# 2015.net
KiCad netlist of a schematic drawn in EAGLE
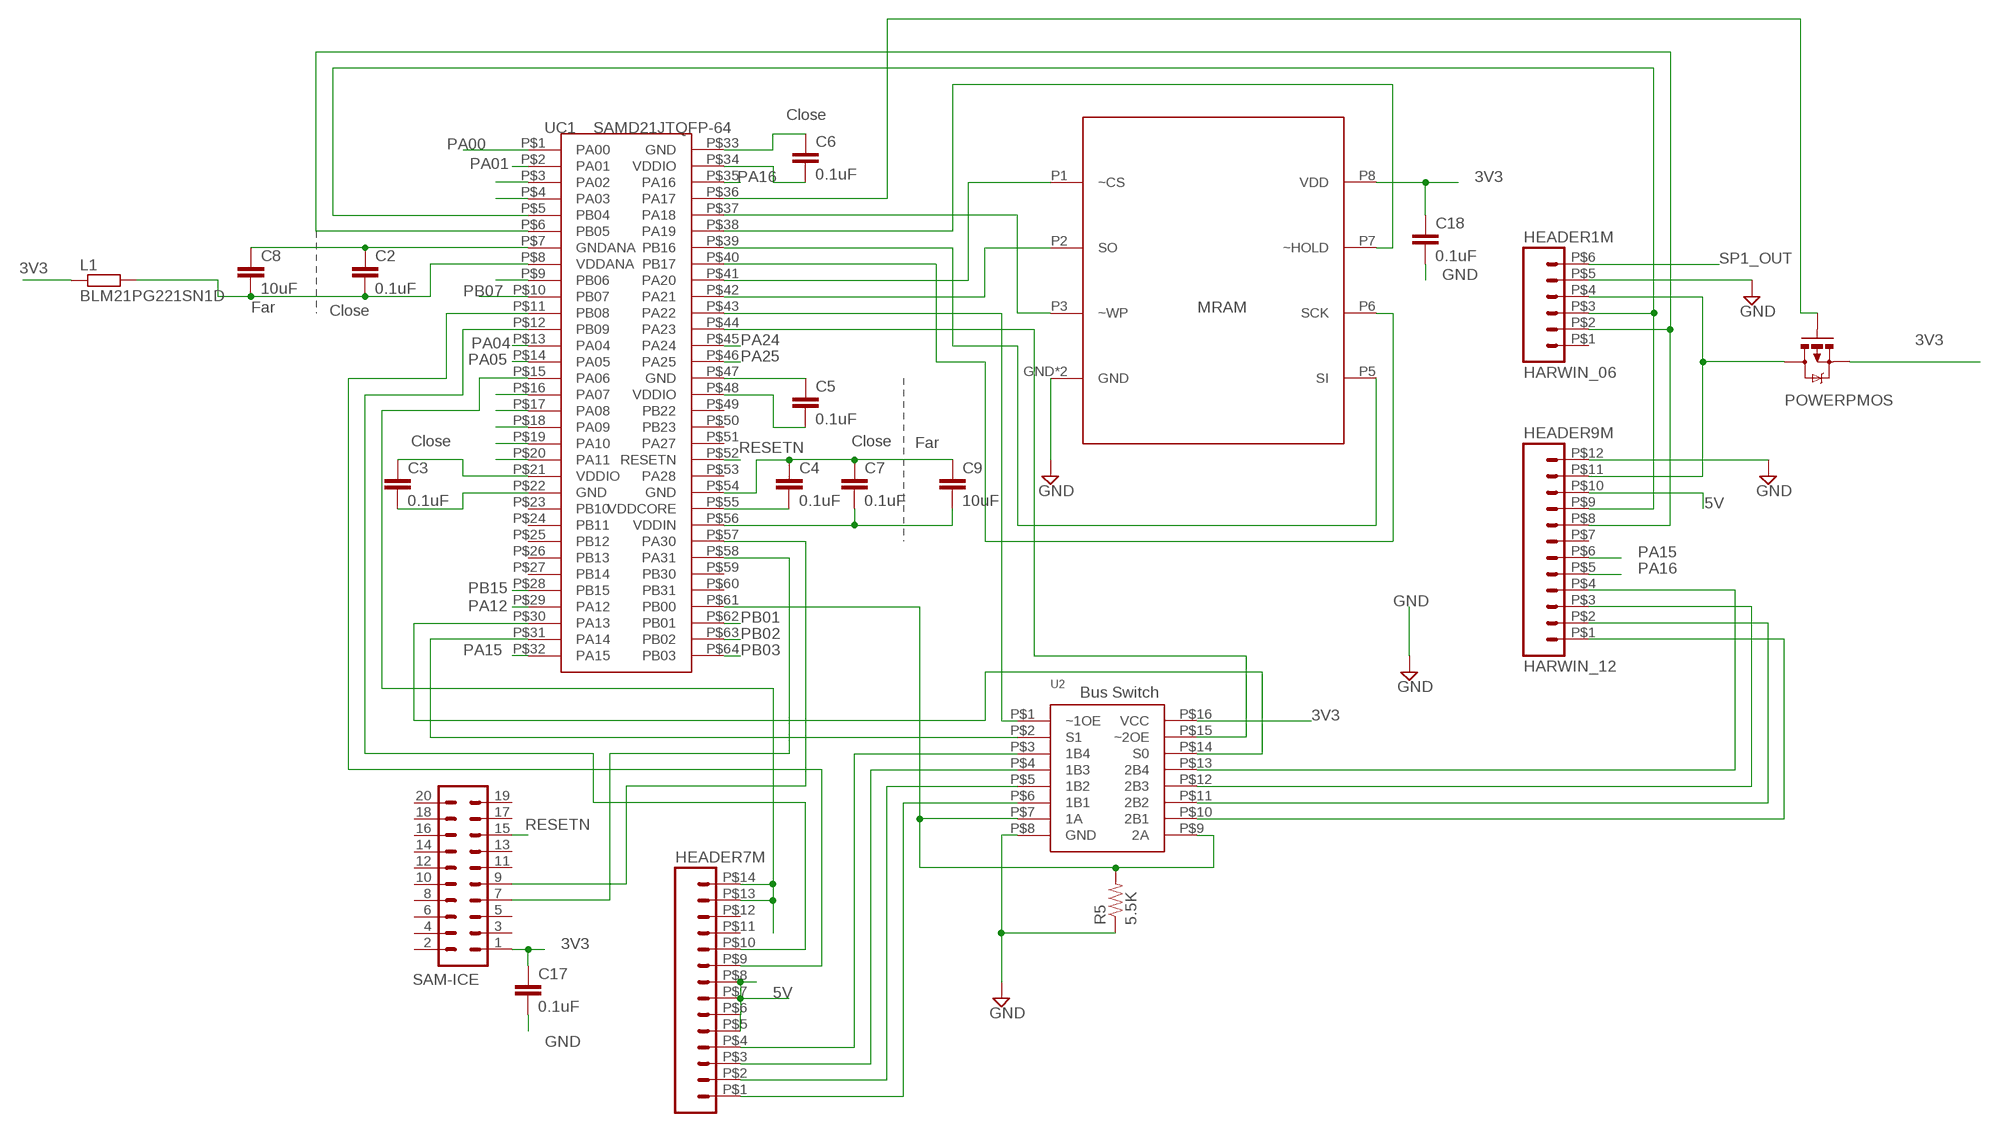
[diagram p0: schematic, sheet 1]
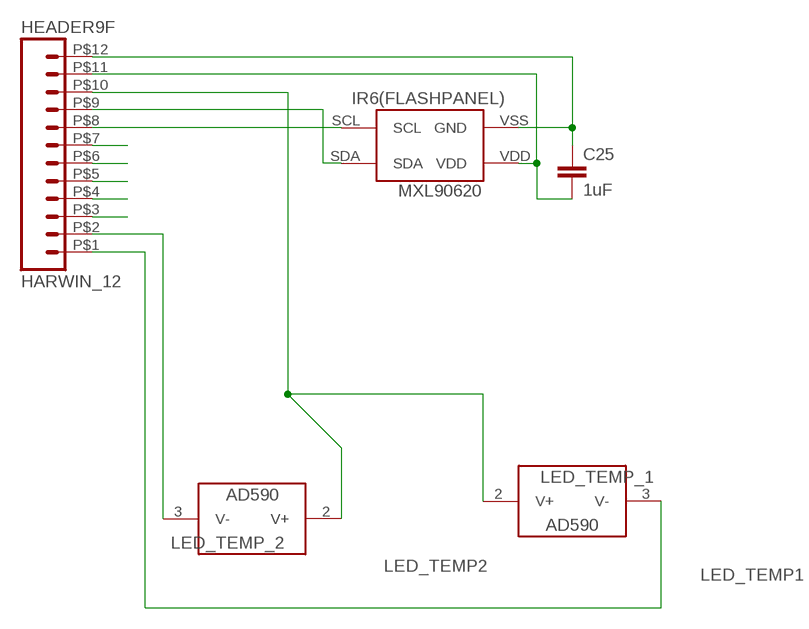
[diagram p1: schematic, sheet 2]
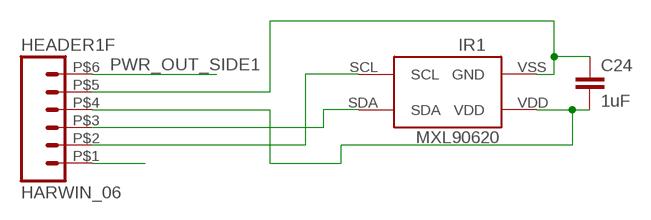
[diagram p2: schematic, sheet 3]
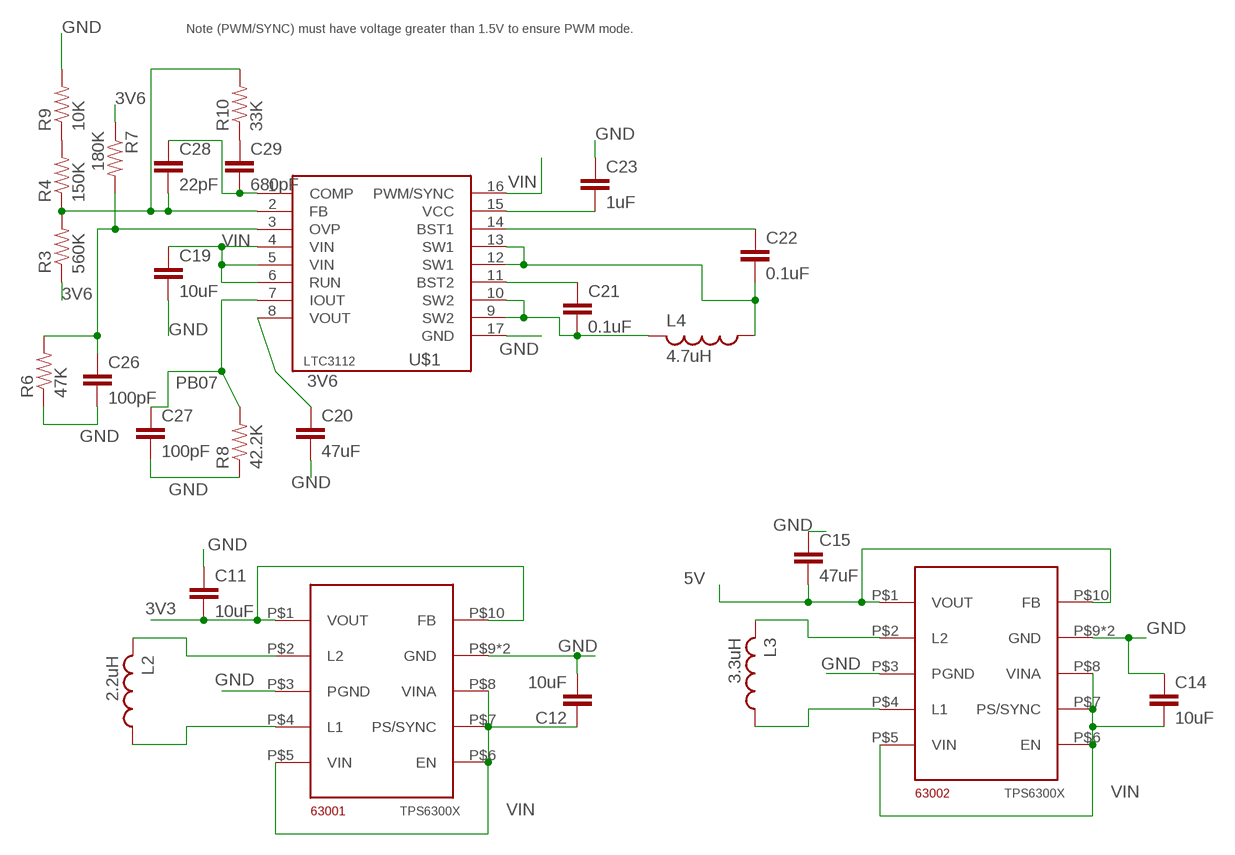
[diagram p3: schematic, sheet 4]
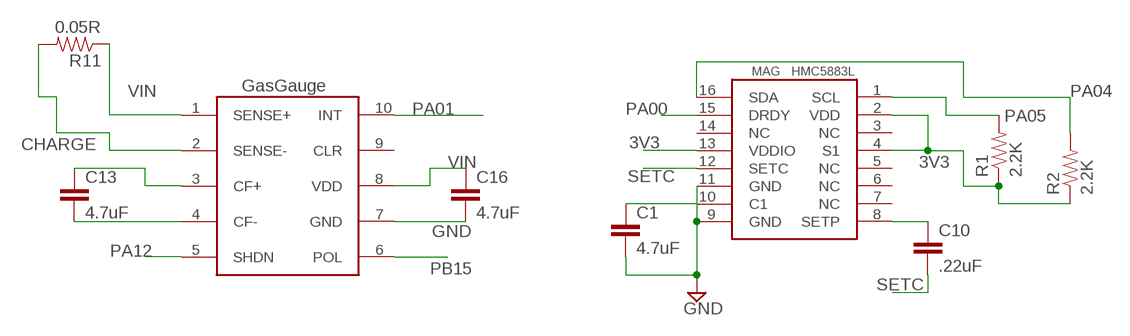
[diagram p4: schematic, sheet 5]
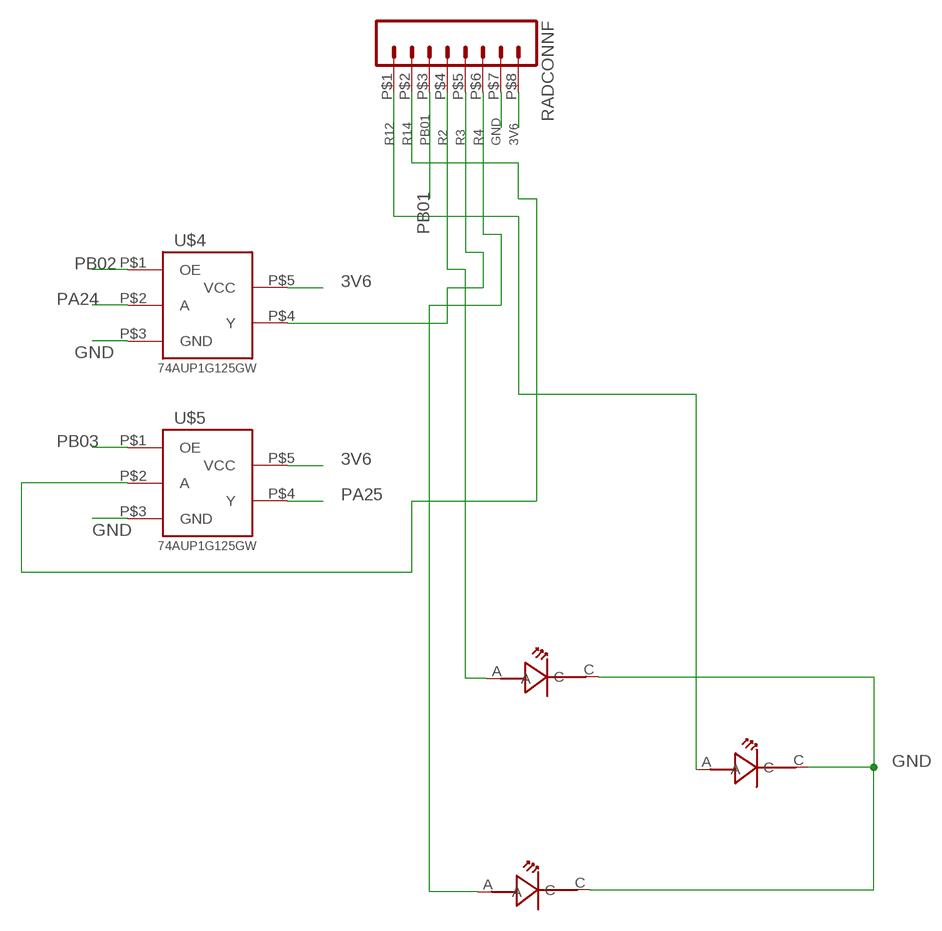
[diagram p5: schematic, sheet 6]
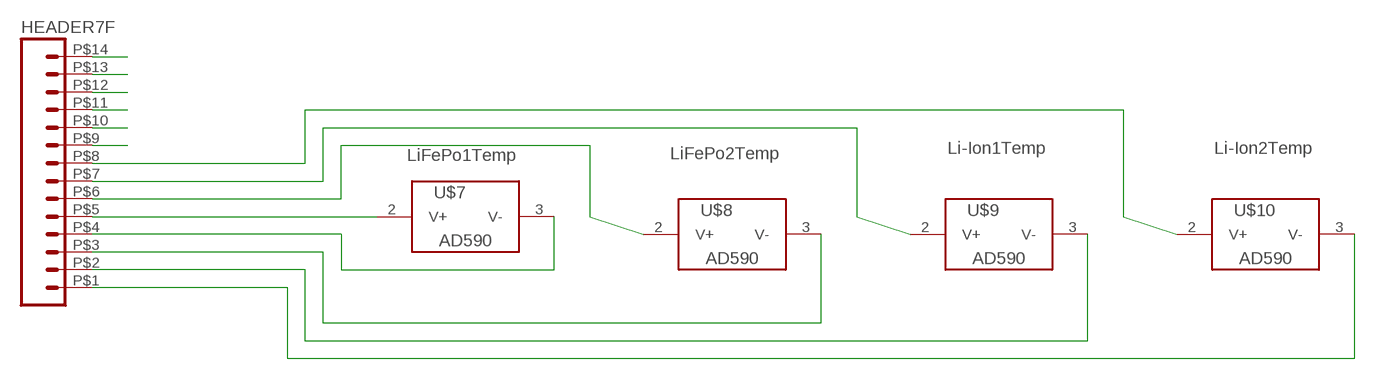
[diagram p6: schematic, sheet 7]

(export (version "E")
  (design (tool "Eeschema 10.0.6"))
  (components
    (comp (ref "63001")
      (value "TPS6300X")
      (footprint "eagle-import:QFN10_POWERPAD")
      (libsource (lib "eagle-import") (part "TPS6300X"))
    )
    (comp (ref "63002")
      (value "TPS6300X")
      (footprint "eagle-import:QFN10_POWERPAD")
      (libsource (lib "eagle-import") (part "TPS6300X"))
    )
    (comp (ref "C11")
      (value "10uF")
      (footprint "eagle-import:0603-CAP")
      (libsource (lib "eagle-import") (part "CAP0603-CAP"))
    )
    (comp (ref "C12")
      (value "10uF")
      (footprint "eagle-import:0603-CAP")
      (libsource (lib "eagle-import") (part "CAP0603-CAP"))
    )
    (comp (ref "C14")
      (value "10uF")
      (footprint "eagle-import:0603-CAP")
      (fields (field (name "MPN") "C1608X5R1A225K080AC"))
      (libsource (lib "eagle-import") (part "CAP0603-CAP"))
    )
    (comp (ref "C15")
      (value "47uF")
      (footprint "eagle-import:0603-CAP")
      (fields (field (name "MPN") "EMK107B7474KA-T"))
      (libsource (lib "eagle-import") (part "CAP0603-CAP"))
    )
    (comp (ref "C19")
      (value "10uF")
      (footprint "eagle-import:0603-CAP")
      (libsource (lib "eagle-import") (part "CAP0603-CAP"))
    )
    (comp (ref "C20")
      (value "47uF")
      (footprint "eagle-import:0805")
      (fields (field (name "MPN") "EMK107B7474KA-T"))
      (libsource (lib "eagle-import") (part "CAP0805"))
    )
    (comp (ref "C21")
      (value "0.1uF")
      (footprint "eagle-import:0603-CAP")
      (fields (field (name "MPN") "0603YC104JAT2A"))
      (libsource (lib "eagle-import") (part "CAP0603-CAP"))
    )
    (comp (ref "C22")
      (value "0.1uF")
      (footprint "eagle-import:0603-CAP")
      (fields (field (name "MPN") "0603YC104JAT2A"))
      (libsource (lib "eagle-import") (part "CAP0603-CAP"))
    )
    (comp (ref "C23")
      (value "1uF")
      (footprint "eagle-import:0603-CAP")
      (libsource (lib "eagle-import") (part "CAP0603-CAP"))
    )
    (comp (ref "C26")
      (value "100pF")
      (footprint "eagle-import:0805")
      (fields (field (name "MF") "AVX CORPORATION") (field (name "MPN") "08051A101J4T4A"))
      (libsource (lib "eagle-import") (part "CAP0805"))
    )
    (comp (ref "C27")
      (value "100pF")
      (footprint "eagle-import:0805")
      (fields (field (name "MF") "AVX CORPORATION") (field (name "MPN") "08051A101J4T4A"))
      (libsource (lib "eagle-import") (part "CAP0805"))
    )
    (comp (ref "C28")
      (value "22pF")
      (footprint "eagle-import:0805")
      (fields (field (name "MF") "AVX CORPORATION") (field (name "MPN") "08051A220JAT2A"))
      (libsource (lib "eagle-import") (part "CAP0805"))
    )
    (comp (ref "C29")
      (value "680pF")
      (footprint "eagle-import:0805")
      (fields (field (name "MPN") "08055C681KAT2A"))
      (libsource (lib "eagle-import") (part "CAP0805"))
    )
    (comp (ref "L2")
      (value "2.2uH")
      (footprint "eagle-import:L3225M")
      (libsource (lib "eagle-import") (part "L-USL3225M"))
    )
    (comp (ref "L3")
      (value "3.3uH")
      (footprint "eagle-import:L3225M")
      (fields (field (name "MPN") "JMK212BJ335KG-T"))
      (libsource (lib "eagle-import") (part "L-USL3225M"))
    )
    (comp (ref "L4")
      (value "4.7uH")
      (footprint "eagle-import:L3225M")
      (libsource (lib "eagle-import") (part "L-USL3225M"))
    )
    (comp (ref "R3")
      (value "560K")
      (footprint "eagle-import:0805")
      (fields (field (name "MPN") "MC01W08051560K"))
      (libsource (lib "eagle-import") (part "RESISTOR"))
    )
    (comp (ref "R4")
      (value "150K")
      (footprint "eagle-import:0805")
      (libsource (lib "eagle-import") (part "RESISTOR"))
    )
    (comp (ref "R6")
      (value "47K")
      (footprint "eagle-import:0805")
      (libsource (lib "eagle-import") (part "RESISTOR"))
    )
    (comp (ref "R7")
      (value "180K")
      (footprint "eagle-import:0805")
      (fields (field (name "MPN") "ERJ-6GEYJ184V"))
      (libsource (lib "eagle-import") (part "RESISTOR"))
    )
    (comp (ref "R8")
      (value "42.2K")
      (footprint "eagle-import:0805")
      (libsource (lib "eagle-import") (part "RESISTOR"))
    )
    (comp (ref "R9")
      (value "10K")
      (footprint "eagle-import:0805")
      (libsource (lib "eagle-import") (part "RESISTOR"))
    )
    (comp (ref "R10")
      (value "33K")
      (footprint "eagle-import:0805")
      (libsource (lib "eagle-import") (part "RESISTOR"))
    )
    (comp (ref "U$1")
      (value "LTC3112")
      (footprint "eagle-import:DHD16")
      (fields (field (name "MPN") "LTC3112EFE#PBF"))
      (libsource (lib "eagle-import") (part "LTC3112"))
    )
    (comp (ref "C2")
      (value "0.1uF")
      (footprint "eagle-import:0805")
      (fields (field (name "MPN") "0603YC104JAT2A"))
      (libsource (lib "eagle-import") (part "CAP0805"))
    )
    (comp (ref "C3")
      (value "0.1uF")
      (footprint "eagle-import:0805")
      (fields (field (name "MPN") "0603YC104JAT2A"))
      (libsource (lib "eagle-import") (part "CAP0805"))
    )
    (comp (ref "C4")
      (value "0.1uF")
      (footprint "eagle-import:0805")
      (fields (field (name "MPN") "0603YC104JAT2A"))
      (libsource (lib "eagle-import") (part "CAP0805"))
    )
    (comp (ref "C5")
      (value "0.1uF")
      (footprint "eagle-import:0805")
      (fields (field (name "MPN") "0603YC104JAT2A"))
      (libsource (lib "eagle-import") (part "CAP0805"))
    )
    (comp (ref "C6")
      (value "0.1uF")
      (footprint "eagle-import:0805")
      (fields (field (name "MPN") "0603YC104JAT2A"))
      (libsource (lib "eagle-import") (part "CAP0805"))
    )
    (comp (ref "C7")
      (value "0.1uF")
      (footprint "eagle-import:0805")
      (fields (field (name "MPN") "0603YC104JAT2A"))
      (libsource (lib "eagle-import") (part "CAP0805"))
    )
    (comp (ref "C8")
      (value "10uF")
      (footprint "eagle-import:0805")
      (fields (field (name "MF") "AVX CORPORATION") (field (name "MPN") "08056D106KAT2A"))
      (libsource (lib "eagle-import") (part "CAP0805"))
    )
    (comp (ref "C9")
      (value "10uF")
      (footprint "eagle-import:0805")
      (fields (field (name "MF") "AVX CORPORATION") (field (name "MPN") "08056D106KAT2A"))
      (libsource (lib "eagle-import") (part "CAP0805"))
    )
    (comp (ref "C17")
      (value "0.1uF")
      (footprint "eagle-import:0805")
      (fields (field (name "MPN") "0603YC104JAT2A"))
      (libsource (lib "eagle-import") (part "CAP0805"))
    )
    (comp (ref "C18")
      (value "0.1uF")
      (footprint "eagle-import:0805")
      (fields (field (name "MPN") "0603YC104JAT2A"))
      (libsource (lib "eagle-import") (part "CAP0805"))
    )
    (comp (ref "HEADER1M")
      (value "HARWIN_06")
      (footprint "eagle-import:HARWIN_DATAMATE_6")
      (libsource (lib "eagle-import") (part "HARWIN_06"))
    )
    (comp (ref "HEADER7M")
      (value "HARWIN_14")
      (footprint "eagle-import:HARWIN_DATAMATE_14")
      (libsource (lib "eagle-import") (part "HARWIN_14"))
    )
    (comp (ref "HEADER9M")
      (value "HARWIN_12")
      (footprint "eagle-import:HARWIN_DATAMATE_12")
      (libsource (lib "eagle-import") (part "HARWIN_12"))
    )
    (comp (ref "L1")
      (value "BLM21PG221SN1D")
      (footprint "eagle-import:R0805")
      (libsource (lib "eagle-import") (part "R-EU_R0805"))
    )
    (comp (ref "R5")
      (value "5.5K")
      (footprint "eagle-import:0805")
      (libsource (lib "eagle-import") (part "RESISTOR"))
    )
    (comp (ref "SAM-ICE")
      (value "IDC_JTAG_CONNECTOR")
      (footprint "eagle-import:2X10")
      (libsource (lib "eagle-import") (part "IDC_JTAG_CONNECTOR"))
    )
    (comp (ref "U$3")
      (value "MRAM")
      (footprint "eagle-import:8PXMO-229")
      (libsource (lib "eagle-import") (part "MR25H10CDC"))
    )
    (comp (ref "U$14")
      (value "POWERPMOS")
      (footprint "eagle-import:SO08")
      (libsource (lib "eagle-import") (part "POWERPMOS"))
    )
    (comp (ref "U2")
      (value "SN74CBTLV3253")
      (footprint "eagle-import:SOIC16R")
      (libsource (lib "eagle-import") (part "SN74CBTLV3253"))
    )
    (comp (ref "UC1")
      (value "SAMD21JTQFP-64")
      (footprint "eagle-import:TQFP-64")
      (libsource (lib "eagle-import") (part "SAMD21JTQFP-64"))
    )
    (comp (ref "C1")
      (value "4.7uF")
      (footprint "eagle-import:0805")
      (fields (field (name "MF") "AVX CORPORATION") (field (name "MPN") "08056D475KAT2A"))
      (libsource (lib "eagle-import") (part "CAP0805"))
    )
    (comp (ref "C10")
      (value ".22uF")
      (footprint "eagle-import:0805")
      (fields (field (name "MF") "AVX CORPORATION") (field (name "MPN") "08053C224KAT2A"))
      (libsource (lib "eagle-import") (part "CAP0805"))
    )
    (comp (ref "C13")
      (value "4.7uF")
      (footprint "eagle-import:0805")
      (fields (field (name "MF") "AVX CORPORATION") (field (name "MPN") "08056D475KAT2A"))
      (libsource (lib "eagle-import") (part "CAP0805"))
    )
    (comp (ref "C16")
      (value "4.7uF")
      (footprint "eagle-import:0805")
      (fields (field (name "MF") "AVX CORPORATION") (field (name "MPN") "08056D475KAT2A"))
      (libsource (lib "eagle-import") (part "CAP0805"))
    )
    (comp (ref "MAG")
      (value "HMC5883L")
      (footprint "eagle-import:HMC5883L")
      (fields (field (name "MPN") "HMC5883L-TR"))
      (libsource (lib "eagle-import") (part "HMC5883L"))
    )
    (comp (ref "R1")
      (value "2.2K")
      (footprint "eagle-import:0805")
      (fields (field (name "MPN") "SR1-0805-222"))
      (libsource (lib "eagle-import") (part "RESISTOR"))
    )
    (comp (ref "R2")
      (value "2.2K")
      (footprint "eagle-import:0805")
      (fields (field (name "MPN") "SR1-0805-222"))
      (libsource (lib "eagle-import") (part "RESISTOR"))
    )
    (comp (ref "R11")
      (value "0.05R")
      (footprint "eagle-import:0805")
      (libsource (lib "eagle-import") (part "RESISTOR"))
    )
    (comp (ref "U$2")
      (value "LTC4150")
      (footprint "eagle-import:MSOP10")
      (fields (field (name "MPN") "LTC4150CMS#PBF"))
      (libsource (lib "eagle-import") (part "LTC4150"))
    )
    (comp (ref "C25")
      (value "1uF")
      (footprint "eagle-import:0805")
      (fields (field (name "MPN") "0805ZC105KAT2A"))
      (libsource (lib "eagle-import") (part "CAP0805"))
    )
    (comp (ref "HEADER9F")
      (value "HARWIN_12")
      (footprint "eagle-import:HARWIN_DATAMATE_12")
      (libsource (lib "eagle-import") (part "HARWIN_12"))
    )
    (comp (ref "IR6(FLASHPANEL)")
      (value "MXL90620")
      (footprint "eagle-import:MXL90620")
      (libsource (lib "eagle-import") (part "MXL90620"))
    )
    (comp (ref "LED_TEMP_1")
      (value "AD590-SOIC-8")
      (footprint "eagle-import:8SOIC")
      (fields (field (name "MPN") "AD590JRZ"))
      (libsource (lib "eagle-import") (part "AD590-SOIC-8"))
    )
    (comp (ref "LED_TEMP_2")
      (value "AD590-SOIC-8")
      (footprint "eagle-import:8SOIC")
      (fields (field (name "MPN") "AD590JRZ"))
      (libsource (lib "eagle-import") (part "AD590-SOIC-8"))
    )
    (comp (ref "HEADER7F")
      (value "HARWIN_14")
      (footprint "eagle-import:HARWIN_DATAMATE_14")
      (libsource (lib "eagle-import") (part "HARWIN_14"))
    )
    (comp (ref "U$7")
      (value "AD590-SOIC-8")
      (footprint "eagle-import:8SOIC")
      (fields (field (name "MPN") "AD590JRZ"))
      (libsource (lib "eagle-import") (part "AD590-SOIC-8"))
    )
    (comp (ref "U$8")
      (value "AD590-SOIC-8")
      (footprint "eagle-import:8SOIC")
      (fields (field (name "MPN") "AD590JRZ"))
      (libsource (lib "eagle-import") (part "AD590-SOIC-8"))
    )
    (comp (ref "U$9")
      (value "AD590-SOIC-8")
      (footprint "eagle-import:8SOIC")
      (fields (field (name "MPN") "AD590JRZ"))
      (libsource (lib "eagle-import") (part "AD590-SOIC-8"))
    )
    (comp (ref "U$10")
      (value "AD590-SOIC-8")
      (footprint "eagle-import:8SOIC")
      (fields (field (name "MPN") "AD590JRZ"))
      (libsource (lib "eagle-import") (part "AD590-SOIC-8"))
    )
    (comp (ref "RADCONNF")
      (value "HARWIN_08")
      (footprint "eagle-import:HARWIN_DATAMATE_08")
      (libsource (lib "eagle-import") (part "HARWIN_08"))
    )
    (comp (ref "U$4")
      (value "74AUP1G125GW")
      (footprint "eagle-import:TSSOP-5")
      (libsource (lib "eagle-import") (part "74AUP1G125GW"))
    )
    (comp (ref "U$5")
      (value "74AUP1G125GW")
      (footprint "eagle-import:TSSOP-5")
      (libsource (lib "eagle-import") (part "74AUP1G125GW"))
    )
    (comp (ref "U$11")
      (value "LT-T673-Q1R2-25-Z")
      (footprint "eagle-import:PLCC-2")
      (libsource (lib "eagle-import") (part "LT-T673-Q1R2-25-Z"))
    )
    (comp (ref "U$12")
      (value "LT-T673-Q1R2-25-Z")
      (footprint "eagle-import:PLCC-2")
      (libsource (lib "eagle-import") (part "LT-T673-Q1R2-25-Z"))
    )
    (comp (ref "U$13")
      (value "LT-T673-Q1R2-25-Z")
      (footprint "eagle-import:PLCC-2")
      (libsource (lib "eagle-import") (part "LT-T673-Q1R2-25-Z"))
    )
    (comp (ref "C24")
      (value "1uF")
      (footprint "eagle-import:0805")
      (fields (field (name "MPN") "0805ZC105KAT2A"))
      (libsource (lib "eagle-import") (part "CAP0805"))
    )
    (comp (ref "HEADER1F")
      (value "HARWIN_06")
      (footprint "eagle-import:HARWIN_DATAMATE_6")
      (libsource (lib "eagle-import") (part "HARWIN_06"))
    )
    (comp (ref "IR1")
      (value "MXL90620")
      (footprint "eagle-import:MXL90620")
      (libsource (lib "eagle-import") (part "MXL90620"))
    )
  )
  (nets
    (net (code "1") (name "3V3") (class "Default")
      (node (ref "63001") (pin "P$1") (pinfunction "VOUT_P$1") (pintype "output"))
      (node (ref "63001") (pin "P$10") (pinfunction "FB_P$10") (pintype "input"))
      (node (ref "C11") (pin "2") (pinfunction "2_2") (pintype "passive"))
      (node (ref "C17") (pin "1") (pinfunction "1_1") (pintype "passive"))
      (node (ref "C18") (pin "1") (pinfunction "1_1") (pintype "passive"))
      (node (ref "C3") (pin "1") (pinfunction "1_1") (pintype "passive"))
      (node (ref "C5") (pin "2") (pinfunction "2_2") (pintype "passive"))
      (node (ref "C6") (pin "2") (pinfunction "2_2") (pintype "passive"))
      (node (ref "C7") (pin "2") (pinfunction "2_2") (pintype "passive"))
      (node (ref "C9") (pin "2") (pinfunction "2_2") (pintype "passive"))
      (node (ref "L1") (pin "1") (pinfunction "1_1") (pintype "passive"))
      (node (ref "MAG") (pin "13") (pinfunction "VDDIO_13") (pintype "bidirectional"))
      (node (ref "MAG") (pin "2") (pinfunction "VDD_2") (pintype "bidirectional"))
      (node (ref "MAG") (pin "4") (pinfunction "S1_4") (pintype "bidirectional"))
      (node (ref "R1") (pin "1") (pinfunction "1_1") (pintype "passive"))
      (node (ref "R2") (pin "1") (pinfunction "1_1") (pintype "passive"))
      (node (ref "SAM-ICE") (pin "1") (pinfunction "1_1") (pintype "passive"))
      (node (ref "U$14") (pin "1") (pinfunction "S_1") (pintype "passive"))
      (node (ref "U$14") (pin "2") (pinfunction "S_2") (pintype "passive"))
      (node (ref "U$14") (pin "3") (pinfunction "S_3") (pintype "passive"))
      (node (ref "U$3") (pin "P8") (pinfunction "VDD_P8") (pintype "bidirectional"))
      (node (ref "U2") (pin "P$16") (pinfunction "VCC_P$16") (pintype "bidirectional"))
      (node (ref "UC1") (pin "P$21") (pinfunction "VDDIO_P$21") (pintype "power_in"))
      (node (ref "UC1") (pin "P$34") (pinfunction "VDDIO_P$34") (pintype "power_in"))
      (node (ref "UC1") (pin "P$48") (pinfunction "VDDIO_P$48") (pintype "power_in"))
      (node (ref "UC1") (pin "P$56") (pinfunction "VDDIN_P$56") (pintype "power_in"))
    )
    (net (code "2") (name "3V6") (class "Default")
      (node (ref "C20") (pin "1") (pinfunction "1_1") (pintype "passive"))
      (node (ref "R3") (pin "1") (pinfunction "1_1") (pintype "passive"))
      (node (ref "R7") (pin "1") (pinfunction "1_1") (pintype "passive"))
      (node (ref "RADCONNF") (pin "P$8") (pinfunction "8_P$8") (pintype "passive"))
      (node (ref "U$1") (pin "8") (pinfunction "VOUT_8") (pintype "bidirectional"))
      (node (ref "U$4") (pin "P$5") (pinfunction "VCC_P$5") (pintype "bidirectional"))
      (node (ref "U$5") (pin "P$5") (pinfunction "VCC_P$5") (pintype "bidirectional"))
    )
    (net (code "3") (name "5V") (class "Default")
      (node (ref "63002") (pin "P$1") (pinfunction "VOUT_P$1") (pintype "output"))
      (node (ref "63002") (pin "P$10") (pinfunction "FB_P$10") (pintype "input"))
      (node (ref "C15") (pin "2") (pinfunction "2_2") (pintype "passive"))
      (node (ref "HEADER7M") (pin "P$5") (pinfunction "5_P$5") (pintype "passive"))
      (node (ref "HEADER7M") (pin "P$6") (pinfunction "6_P$6") (pintype "passive"))
      (node (ref "HEADER7M") (pin "P$7") (pinfunction "7_P$7") (pintype "passive"))
      (node (ref "HEADER7M") (pin "P$8") (pinfunction "8_P$8") (pintype "passive"))
      (node (ref "HEADER9M") (pin "P$10") (pinfunction "10_P$10") (pintype "passive"))
    )
    (net (code "4") (name "CHARGE") (class "Default")
      (node (ref "R11") (pin "2") (pinfunction "2_2") (pintype "passive"))
      (node (ref "U$2") (pin "2") (pinfunction "SENSE-_2") (pintype "bidirectional"))
    )
    (net (code "5") (name "GND") (class "Default")
      (node (ref "63001") (pin "P$3") (pinfunction "PGND_P$3") (pintype "input"))
      (node (ref "63001") (pin "P$9") (pinfunction "GND_P$9") (pintype "input"))
      (node (ref "63001") (pin "PAD") (pinfunction "GND_PAD") (pintype "input"))
      (node (ref "63002") (pin "P$3") (pinfunction "PGND_P$3") (pintype "input"))
      (node (ref "63002") (pin "P$9") (pinfunction "GND_P$9") (pintype "input"))
      (node (ref "63002") (pin "PAD") (pinfunction "GND_PAD") (pintype "input"))
      (node (ref "C1") (pin "2") (pinfunction "2_2") (pintype "passive"))
      (node (ref "C11") (pin "1") (pinfunction "1_1") (pintype "passive"))
      (node (ref "C12") (pin "2") (pinfunction "2_2") (pintype "passive"))
      (node (ref "C14") (pin "1") (pinfunction "1_1") (pintype "passive"))
      (node (ref "C15") (pin "1") (pinfunction "1_1") (pintype "passive"))
      (node (ref "C16") (pin "2") (pinfunction "2_2") (pintype "passive"))
      (node (ref "C17") (pin "2") (pinfunction "2_2") (pintype "passive"))
      (node (ref "C18") (pin "2") (pinfunction "2_2") (pintype "passive"))
      (node (ref "C19") (pin "2") (pinfunction "2_2") (pintype "passive"))
      (node (ref "C2") (pin "1") (pinfunction "1_1") (pintype "passive"))
      (node (ref "C20") (pin "2") (pinfunction "2_2") (pintype "passive"))
      (node (ref "C23") (pin "1") (pinfunction "1_1") (pintype "passive"))
      (node (ref "C26") (pin "2") (pinfunction "2_2") (pintype "passive"))
      (node (ref "C27") (pin "2") (pinfunction "2_2") (pintype "passive"))
      (node (ref "C4") (pin "1") (pinfunction "1_1") (pintype "passive"))
      (node (ref "C5") (pin "1") (pinfunction "1_1") (pintype "passive"))
      (node (ref "C6") (pin "1") (pinfunction "1_1") (pintype "passive"))
      (node (ref "C7") (pin "1") (pinfunction "1_1") (pintype "passive"))
      (node (ref "C8") (pin "1") (pinfunction "1_1") (pintype "passive"))
      (node (ref "C9") (pin "1") (pinfunction "1_1") (pintype "passive"))
      (node (ref "HEADER1M") (pin "P$5") (pinfunction "5_P$5") (pintype "passive"))
      (node (ref "HEADER9M") (pin "P$12") (pinfunction "12_P$12") (pintype "passive"))
      (node (ref "MAG") (pin "11") (pinfunction "GND_11") (pintype "bidirectional"))
      (node (ref "MAG") (pin "9") (pinfunction "GND_9") (pintype "bidirectional"))
      (node (ref "R5") (pin "1") (pinfunction "1_1") (pintype "passive"))
      (node (ref "R6") (pin "1") (pinfunction "1_1") (pintype "passive"))
      (node (ref "R8") (pin "1") (pinfunction "1_1") (pintype "passive"))
      (node (ref "R9") (pin "2") (pinfunction "2_2") (pintype "passive"))
      (node (ref "RADCONNF") (pin "P$7") (pinfunction "7_P$7") (pintype "passive"))
      (node (ref "U$1") (pin "17") (pinfunction "GND_17") (pintype "bidirectional"))
      (node (ref "U$11") (pin "C") (pinfunction "C_C") (pintype "bidirectional"))
      (node (ref "U$12") (pin "C") (pinfunction "C_C") (pintype "bidirectional"))
      (node (ref "U$13") (pin "C") (pinfunction "C_C") (pintype "bidirectional"))
      (node (ref "U$2") (pin "7") (pinfunction "GND_7") (pintype "bidirectional"))
      (node (ref "U$3") (pin "GND") (pinfunction "GND_GND") (pintype "bidirectional"))
      (node (ref "U$3") (pin "P4") (pinfunction "GND_P4") (pintype "bidirectional"))
      (node (ref "U$4") (pin "P$3") (pinfunction "GND_P$3") (pintype "bidirectional"))
      (node (ref "U$5") (pin "P$3") (pinfunction "GND_P$3") (pintype "bidirectional"))
      (node (ref "U2") (pin "P$8") (pinfunction "GND_P$8") (pintype "bidirectional"))
      (node (ref "UC1") (pin "P$33") (pinfunction "GND_P$33") (pintype "power_in"))
      (node (ref "UC1") (pin "P$47") (pinfunction "GND_P$47") (pintype "power_in"))
      (node (ref "UC1") (pin "P$54") (pinfunction "GND_P$54") (pintype "power_in"))
      (node (ref "UC1") (pin "P$7") (pinfunction "GNDANA_P$7") (pintype "power_in"))
    )
    (net (code "6") (name "Net-(63001-L1)") (class "Default")
      (node (ref "63001") (pin "P$4") (pinfunction "L1_P$4") (pintype "input"))
      (node (ref "L2") (pin "1") (pinfunction "1_1") (pintype "passive"))
    )
    (net (code "7") (name "Net-(63001-L2)") (class "Default")
      (node (ref "63001") (pin "P$2") (pinfunction "L2_P$2") (pintype "input"))
      (node (ref "L2") (pin "2") (pinfunction "2_2") (pintype "passive"))
    )
    (net (code "8") (name "Net-(63002-L1)") (class "Default")
      (node (ref "63002") (pin "P$4") (pinfunction "L1_P$4") (pintype "input"))
      (node (ref "L3") (pin "1") (pinfunction "1_1") (pintype "passive"))
    )
    (net (code "9") (name "Net-(63002-L2)") (class "Default")
      (node (ref "63002") (pin "P$2") (pinfunction "L2_P$2") (pintype "input"))
      (node (ref "L3") (pin "2") (pinfunction "2_2") (pintype "passive"))
    )
    (net (code "10") (name "Net-(C3-Pad2)") (class "Default")
      (node (ref "C3") (pin "2") (pinfunction "2_2") (pintype "passive"))
      (node (ref "UC1") (pin "P$22") (pinfunction "GND_P$22") (pintype "power_in"))
    )
    (net (code "11") (name "Net-(C21-Pad2)") (class "Default")
      (node (ref "C21") (pin "2") (pinfunction "2_2") (pintype "passive"))
      (node (ref "L4") (pin "2") (pinfunction "2_2") (pintype "passive"))
      (node (ref "U$1") (pin "10") (pinfunction "SW2_10") (pintype "bidirectional"))
      (node (ref "U$1") (pin "9") (pinfunction "SW2_9") (pintype "bidirectional"))
    )
    (net (code "12") (name "Net-(C22-Pad2)") (class "Default")
      (node (ref "C22") (pin "2") (pinfunction "2_2") (pintype "passive"))
      (node (ref "L4") (pin "1") (pinfunction "1_1") (pintype "passive"))
      (node (ref "U$1") (pin "12") (pinfunction "SW1_12") (pintype "bidirectional"))
      (node (ref "U$1") (pin "13") (pinfunction "SW1_13") (pintype "bidirectional"))
    )
    (net (code "13") (name "Net-(C29-Pad1)") (class "Default")
      (node (ref "C29") (pin "1") (pinfunction "1_1") (pintype "passive"))
      (node (ref "R10") (pin "1") (pinfunction "1_1") (pintype "passive"))
    )
    (net (code "14") (name "Net-(HEADER1F-2)") (class "Default")
      (node (ref "HEADER1F") (pin "P$2") (pinfunction "2_P$2") (pintype "passive"))
      (node (ref "IR1") (pin "SCL") (pinfunction "SCL_SCL") (pintype "bidirectional"))
    )
    (net (code "15") (name "Net-(HEADER1F-3)") (class "Default")
      (node (ref "HEADER1F") (pin "P$3") (pinfunction "3_P$3") (pintype "passive"))
      (node (ref "IR1") (pin "SDA") (pinfunction "SDA_SDA") (pintype "bidirectional"))
    )
    (net (code "16") (name "Net-(HEADER1F-4)") (class "Default")
      (node (ref "C24") (pin "2") (pinfunction "2_2") (pintype "passive"))
      (node (ref "HEADER1F") (pin "P$4") (pinfunction "4_P$4") (pintype "passive"))
      (node (ref "IR1") (pin "VDD") (pinfunction "VDD_VDD") (pintype "bidirectional"))
    )
    (net (code "17") (name "Net-(HEADER1F-5)") (class "Default")
      (node (ref "C24") (pin "1") (pinfunction "1_1") (pintype "passive"))
      (node (ref "HEADER1F") (pin "P$5") (pinfunction "5_P$5") (pintype "passive"))
      (node (ref "IR1") (pin "VSS") (pinfunction "GND_VSS") (pintype "bidirectional"))
    )
    (net (code "18") (name "Net-(HEADER1M-2)") (class "Default")
      (node (ref "HEADER1M") (pin "P$2") (pinfunction "2_P$2") (pintype "passive"))
      (node (ref "HEADER9M") (pin "P$8") (pinfunction "8_P$8") (pintype "passive"))
      (node (ref "UC1") (pin "P$6") (pinfunction "PB05_P$6") (pintype "bidirectional"))
    )
    (net (code "19") (name "Net-(HEADER1M-3)") (class "Default")
      (node (ref "HEADER1M") (pin "P$3") (pinfunction "3_P$3") (pintype "passive"))
      (node (ref "HEADER9M") (pin "P$9") (pinfunction "9_P$9") (pintype "passive"))
      (node (ref "UC1") (pin "P$5") (pinfunction "PB04_P$5") (pintype "bidirectional"))
    )
    (net (code "20") (name "Net-(HEADER1M-4)") (class "Default")
      (node (ref "HEADER1M") (pin "P$4") (pinfunction "4_P$4") (pintype "passive"))
      (node (ref "HEADER9M") (pin "P$11") (pinfunction "11_P$11") (pintype "passive"))
      (node (ref "U$14") (pin "5") (pinfunction "D_5") (pintype "passive"))
      (node (ref "U$14") (pin "6") (pinfunction "D_6") (pintype "passive"))
      (node (ref "U$14") (pin "7") (pinfunction "D_7") (pintype "passive"))
      (node (ref "U$14") (pin "8") (pinfunction "D_8") (pintype "passive"))
    )
    (net (code "21") (name "Net-(HEADER7F-1)") (class "Default")
      (node (ref "HEADER7F") (pin "P$1") (pinfunction "1_P$1") (pintype "passive"))
      (node (ref "U$10") (pin "3") (pinfunction "V-_3") (pintype "bidirectional"))
    )
    (net (code "22") (name "Net-(HEADER7F-2)") (class "Default")
      (node (ref "HEADER7F") (pin "P$2") (pinfunction "2_P$2") (pintype "passive"))
      (node (ref "U$9") (pin "3") (pinfunction "V-_3") (pintype "bidirectional"))
    )
    (net (code "23") (name "Net-(HEADER7F-3)") (class "Default")
      (node (ref "HEADER7F") (pin "P$3") (pinfunction "3_P$3") (pintype "passive"))
      (node (ref "U$8") (pin "3") (pinfunction "V-_3") (pintype "bidirectional"))
    )
    (net (code "24") (name "Net-(HEADER7F-4)") (class "Default")
      (node (ref "HEADER7F") (pin "P$4") (pinfunction "4_P$4") (pintype "passive"))
      (node (ref "U$7") (pin "3") (pinfunction "V-_3") (pintype "bidirectional"))
    )
    (net (code "25") (name "Net-(HEADER7F-5)") (class "Default")
      (node (ref "HEADER7F") (pin "P$5") (pinfunction "5_P$5") (pintype "passive"))
      (node (ref "U$7") (pin "2") (pinfunction "V+_2") (pintype "bidirectional"))
    )
    (net (code "26") (name "Net-(HEADER7F-6)") (class "Default")
      (node (ref "HEADER7F") (pin "P$6") (pinfunction "6_P$6") (pintype "passive"))
      (node (ref "U$8") (pin "2") (pinfunction "V+_2") (pintype "bidirectional"))
    )
    (net (code "27") (name "Net-(HEADER7F-7)") (class "Default")
      (node (ref "HEADER7F") (pin "P$7") (pinfunction "7_P$7") (pintype "passive"))
      (node (ref "U$9") (pin "2") (pinfunction "V+_2") (pintype "bidirectional"))
    )
    (net (code "28") (name "Net-(HEADER7F-8)") (class "Default")
      (node (ref "HEADER7F") (pin "P$8") (pinfunction "8_P$8") (pintype "passive"))
      (node (ref "U$10") (pin "2") (pinfunction "V+_2") (pintype "bidirectional"))
    )
    (net (code "29") (name "Net-(HEADER7M-1)") (class "Default")
      (node (ref "HEADER7M") (pin "P$1") (pinfunction "1_P$1") (pintype "passive"))
      (node (ref "U2") (pin "P$6") (pinfunction "1B1_P$6") (pintype "bidirectional"))
    )
    (net (code "30") (name "Net-(HEADER7M-2)") (class "Default")
      (node (ref "HEADER7M") (pin "P$2") (pinfunction "2_P$2") (pintype "passive"))
      (node (ref "U2") (pin "P$5") (pinfunction "1B2_P$5") (pintype "bidirectional"))
    )
    (net (code "31") (name "Net-(HEADER7M-3)") (class "Default")
      (node (ref "HEADER7M") (pin "P$3") (pinfunction "3_P$3") (pintype "passive"))
      (node (ref "U2") (pin "P$4") (pinfunction "1B3_P$4") (pintype "bidirectional"))
    )
    (net (code "32") (name "Net-(HEADER7M-4)") (class "Default")
      (node (ref "HEADER7M") (pin "P$4") (pinfunction "4_P$4") (pintype "passive"))
      (node (ref "U2") (pin "P$3") (pinfunction "1B4_P$3") (pintype "bidirectional"))
    )
    (net (code "33") (name "Net-(HEADER7M-9)") (class "Default")
      (node (ref "HEADER7M") (pin "P$9") (pinfunction "9_P$9") (pintype "passive"))
      (node (ref "UC1") (pin "P$11") (pinfunction "PB08_P$11") (pintype "bidirectional"))
    )
    (net (code "34") (name "Net-(HEADER7M-10)") (class "Default")
      (node (ref "HEADER7M") (pin "P$10") (pinfunction "10_P$10") (pintype "passive"))
      (node (ref "UC1") (pin "P$12") (pinfunction "PB09_P$12") (pintype "bidirectional"))
    )
    (net (code "35") (name "Net-(HEADER7M-13)") (class "Default")
      (node (ref "HEADER7M") (pin "P$13") (pinfunction "13_P$13") (pintype "passive"))
      (node (ref "HEADER7M") (pin "P$14") (pinfunction "14_P$14") (pintype "passive"))
      (node (ref "UC1") (pin "P$15") (pinfunction "PA06_P$15") (pintype "bidirectional"))
    )
    (net (code "36") (name "Net-(HEADER9F-1)") (class "Default")
      (node (ref "HEADER9F") (pin "P$1") (pinfunction "1_P$1") (pintype "passive"))
      (node (ref "LED_TEMP_1") (pin "3") (pinfunction "V-_3") (pintype "bidirectional"))
    )
    (net (code "37") (name "Net-(HEADER9F-2)") (class "Default")
      (node (ref "HEADER9F") (pin "P$2") (pinfunction "2_P$2") (pintype "passive"))
      (node (ref "LED_TEMP_2") (pin "3") (pinfunction "V-_3") (pintype "bidirectional"))
    )
    (net (code "38") (name "Net-(HEADER9F-8)") (class "Default")
      (node (ref "HEADER9F") (pin "P$8") (pinfunction "8_P$8") (pintype "passive"))
      (node (ref "IR6(FLASHPANEL)") (pin "SCL") (pinfunction "SCL_SCL") (pintype "bidirectional"))
    )
    (net (code "39") (name "Net-(HEADER9F-9)") (class "Default")
      (node (ref "HEADER9F") (pin "P$9") (pinfunction "9_P$9") (pintype "passive"))
      (node (ref "IR6(FLASHPANEL)") (pin "SDA") (pinfunction "SDA_SDA") (pintype "bidirectional"))
    )
    (net (code "40") (name "Net-(HEADER9F-10)") (class "Default")
      (node (ref "HEADER9F") (pin "P$10") (pinfunction "10_P$10") (pintype "passive"))
      (node (ref "LED_TEMP_1") (pin "2") (pinfunction "V+_2") (pintype "bidirectional"))
      (node (ref "LED_TEMP_2") (pin "2") (pinfunction "V+_2") (pintype "bidirectional"))
    )
    (net (code "41") (name "Net-(HEADER9F-11)") (class "Default")
      (node (ref "C25") (pin "2") (pinfunction "2_2") (pintype "passive"))
      (node (ref "HEADER9F") (pin "P$11") (pinfunction "11_P$11") (pintype "passive"))
      (node (ref "IR6(FLASHPANEL)") (pin "VDD") (pinfunction "VDD_VDD") (pintype "bidirectional"))
    )
    (net (code "42") (name "Net-(HEADER9F-12)") (class "Default")
      (node (ref "C25") (pin "1") (pinfunction "1_1") (pintype "passive"))
      (node (ref "HEADER9F") (pin "P$12") (pinfunction "12_P$12") (pintype "passive"))
      (node (ref "IR6(FLASHPANEL)") (pin "VSS") (pinfunction "GND_VSS") (pintype "bidirectional"))
    )
    (net (code "43") (name "Net-(HEADER9M-1)") (class "Default")
      (node (ref "HEADER9M") (pin "P$1") (pinfunction "1_P$1") (pintype "passive"))
      (node (ref "U2") (pin "P$10") (pinfunction "2B1_P$10") (pintype "bidirectional"))
    )
    (net (code "44") (name "Net-(HEADER9M-2)") (class "Default")
      (node (ref "HEADER9M") (pin "P$2") (pinfunction "2_P$2") (pintype "passive"))
      (node (ref "U2") (pin "P$11") (pinfunction "2B2_P$11") (pintype "bidirectional"))
    )
    (net (code "45") (name "Net-(HEADER9M-3)") (class "Default")
      (node (ref "HEADER9M") (pin "P$3") (pinfunction "3_P$3") (pintype "passive"))
      (node (ref "U2") (pin "P$12") (pinfunction "2B3_P$12") (pintype "bidirectional"))
    )
    (net (code "46") (name "Net-(HEADER9M-4)") (class "Default")
      (node (ref "HEADER9M") (pin "P$4") (pinfunction "4_P$4") (pintype "passive"))
      (node (ref "U2") (pin "P$13") (pinfunction "2B4_P$13") (pintype "bidirectional"))
    )
    (net (code "47") (name "Net-(MAG-C1)") (class "Default")
      (node (ref "C1") (pin "1") (pinfunction "1_1") (pintype "passive"))
      (node (ref "MAG") (pin "10") (pinfunction "C1_10") (pintype "bidirectional"))
    )
    (net (code "48") (name "Net-(MAG-SETP)") (class "Default")
      (node (ref "C10") (pin "1") (pinfunction "1_1") (pintype "passive"))
      (node (ref "MAG") (pin "8") (pinfunction "SETP_8") (pintype "bidirectional"))
    )
    (net (code "49") (name "Net-(R4-Pad2)") (class "Default")
      (node (ref "R4") (pin "2") (pinfunction "2_2") (pintype "passive"))
      (node (ref "R9") (pin "1") (pinfunction "1_1") (pintype "passive"))
    )
    (net (code "50") (name "Net-(U$1-BST1)") (class "Default")
      (node (ref "C22") (pin "1") (pinfunction "1_1") (pintype "passive"))
      (node (ref "U$1") (pin "14") (pinfunction "BST1_14") (pintype "bidirectional"))
    )
    (net (code "51") (name "Net-(U$1-BST2)") (class "Default")
      (node (ref "C21") (pin "1") (pinfunction "1_1") (pintype "passive"))
      (node (ref "U$1") (pin "11") (pinfunction "BST2_11") (pintype "bidirectional"))
    )
    (net (code "52") (name "Net-(U$1-COMP)") (class "Default")
      (node (ref "C28") (pin "1") (pinfunction "1_1") (pintype "passive"))
      (node (ref "C29") (pin "2") (pinfunction "2_2") (pintype "passive"))
      (node (ref "U$1") (pin "1") (pinfunction "COMP_1") (pintype "bidirectional"))
    )
    (net (code "53") (name "Net-(U$1-FB)") (class "Default")
      (node (ref "C28") (pin "2") (pinfunction "2_2") (pintype "passive"))
      (node (ref "R10") (pin "2") (pinfunction "2_2") (pintype "passive"))
      (node (ref "R3") (pin "2") (pinfunction "2_2") (pintype "passive"))
      (node (ref "R4") (pin "1") (pinfunction "1_1") (pintype "passive"))
      (node (ref "U$1") (pin "2") (pinfunction "FB_2") (pintype "bidirectional"))
    )
    (net (code "54") (name "Net-(U$1-OVP)") (class "Default")
      (node (ref "C26") (pin "1") (pinfunction "1_1") (pintype "passive"))
      (node (ref "R6") (pin "2") (pinfunction "2_2") (pintype "passive"))
      (node (ref "R7") (pin "2") (pinfunction "2_2") (pintype "passive"))
      (node (ref "U$1") (pin "3") (pinfunction "OVP_3") (pintype "bidirectional"))
    )
    (net (code "55") (name "Net-(U$1-VCC)") (class "Default")
      (node (ref "C23") (pin "2") (pinfunction "2_2") (pintype "passive"))
      (node (ref "U$1") (pin "15") (pinfunction "VCC_15") (pintype "bidirectional"))
    )
    (net (code "56") (name "Net-(U$2-CF+)") (class "Default")
      (node (ref "C13") (pin "1") (pinfunction "1_1") (pintype "passive"))
      (node (ref "U$2") (pin "3") (pinfunction "CF+_3") (pintype "bidirectional"))
    )
    (net (code "57") (name "Net-(U$2-CF-)") (class "Default")
      (node (ref "C13") (pin "2") (pinfunction "2_2") (pintype "passive"))
      (node (ref "U$2") (pin "4") (pinfunction "CF-_4") (pintype "bidirectional"))
    )
    (net (code "58") (name "Net-(U$3-SCK)") (class "Default")
      (node (ref "U$3") (pin "P6") (pinfunction "SCK_P6") (pintype "bidirectional"))
      (node (ref "UC1") (pin "P$40") (pinfunction "PB17_P$40") (pintype "bidirectional"))
    )
    (net (code "59") (name "Net-(U$3-SI)") (class "Default")
      (node (ref "U$3") (pin "P5") (pinfunction "SI_P5") (pintype "bidirectional"))
      (node (ref "UC1") (pin "P$39") (pinfunction "PB16_P$39") (pintype "bidirectional"))
    )
    (net (code "60") (name "Net-(U$3-SO)") (class "Default")
      (node (ref "U$3") (pin "P2") (pinfunction "SO_P2") (pintype "bidirectional"))
      (node (ref "UC1") (pin "P$42") (pinfunction "PA21_P$42") (pintype "bidirectional"))
    )
    (net (code "61") (name "Net-(U$3-~{CS})") (class "Default")
      (node (ref "U$3") (pin "P1") (pinfunction "~{CS}_P1") (pintype "bidirectional"))
      (node (ref "UC1") (pin "P$41") (pinfunction "PA20_P$41") (pintype "bidirectional"))
    )
    (net (code "62") (name "Net-(U$3-~{HOLD})") (class "Default")
      (node (ref "U$3") (pin "P7") (pinfunction "~{HOLD}_P7") (pintype "bidirectional"))
      (node (ref "UC1") (pin "P$38") (pinfunction "PA19_P$38") (pintype "bidirectional"))
    )
    (net (code "63") (name "Net-(U$3-~{WP})") (class "Default")
      (node (ref "U$3") (pin "P3") (pinfunction "~{WP}_P3") (pintype "bidirectional"))
      (node (ref "UC1") (pin "P$37") (pinfunction "PA18_P$37") (pintype "bidirectional"))
    )
    (net (code "64") (name "Net-(U$14-G)") (class "Default")
      (node (ref "U$14") (pin "4") (pinfunction "G_4") (pintype "passive"))
      (node (ref "UC1") (pin "P$36") (pinfunction "PA17_P$36") (pintype "bidirectional"))
    )
    (net (code "65") (name "Net-(U2-1A)") (class "Default")
      (node (ref "R5") (pin "2") (pinfunction "2_2") (pintype "passive"))
      (node (ref "U2") (pin "P$7") (pinfunction "1A_P$7") (pintype "bidirectional"))
      (node (ref "U2") (pin "P$9") (pinfunction "2A_P$9") (pintype "bidirectional"))
      (node (ref "UC1") (pin "P$61") (pinfunction "PB00_P$61") (pintype "bidirectional"))
    )
    (net (code "66") (name "Net-(U2-S0)") (class "Default")
      (node (ref "U2") (pin "P$14") (pinfunction "S0_P$14") (pintype "bidirectional"))
      (node (ref "UC1") (pin "P$30") (pinfunction "PA13_P$30") (pintype "bidirectional"))
    )
    (net (code "67") (name "Net-(U2-S1)") (class "Default")
      (node (ref "U2") (pin "P$2") (pinfunction "S1_P$2") (pintype "bidirectional"))
      (node (ref "UC1") (pin "P$31") (pinfunction "PA14_P$31") (pintype "bidirectional"))
    )
    (net (code "68") (name "Net-(U2-~{1OE})") (class "Default")
      (node (ref "U2") (pin "P$1") (pinfunction "~{1OE}_P$1") (pintype "bidirectional"))
      (node (ref "UC1") (pin "P$43") (pinfunction "PA22_P$43") (pintype "bidirectional"))
    )
    (net (code "69") (name "Net-(U2-~{2OE})") (class "Default")
      (node (ref "U2") (pin "P$15") (pinfunction "~{2OE}_P$15") (pintype "bidirectional"))
      (node (ref "UC1") (pin "P$44") (pinfunction "PA23_P$44") (pintype "bidirectional"))
    )
    (net (code "70") (name "Net-(UC1-PA30)") (class "Default")
      (node (ref "SAM-ICE") (pin "9") (pinfunction "9_9") (pintype "passive"))
      (node (ref "UC1") (pin "P$57") (pinfunction "PA30_P$57") (pintype "bidirectional"))
    )
    (net (code "71") (name "Net-(UC1-PA31)") (class "Default")
      (node (ref "SAM-ICE") (pin "7") (pinfunction "7_7") (pintype "passive"))
      (node (ref "UC1") (pin "P$58") (pinfunction "PA31_P$58") (pintype "bidirectional"))
    )
    (net (code "72") (name "Net-(UC1-VDDANA)") (class "Default")
      (node (ref "C2") (pin "2") (pinfunction "2_2") (pintype "passive"))
      (node (ref "C8") (pin "2") (pinfunction "2_2") (pintype "passive"))
      (node (ref "L1") (pin "2") (pinfunction "2_2") (pintype "passive"))
      (node (ref "UC1") (pin "P$8") (pinfunction "VDDANA_P$8") (pintype "power_in"))
    )
    (net (code "73") (name "Net-(UC1-VDDCORE)") (class "Default")
      (node (ref "C4") (pin "2") (pinfunction "2_2") (pintype "passive"))
      (node (ref "UC1") (pin "P$55") (pinfunction "VDDCORE_P$55") (pintype "power_in"))
    )
    (net (code "74") (name "PA00") (class "Default")
      (node (ref "MAG") (pin "15") (pinfunction "DRDY_15") (pintype "bidirectional"))
      (node (ref "UC1") (pin "P$1") (pinfunction "PA00_P$1") (pintype "bidirectional"))
    )
    (net (code "75") (name "PA01") (class "Default")
      (node (ref "U$2") (pin "10") (pinfunction "INT_10") (pintype "bidirectional"))
      (node (ref "UC1") (pin "P$2") (pinfunction "PA01_P$2") (pintype "bidirectional"))
    )
    (net (code "76") (name "PA04") (class "Default")
      (node (ref "MAG") (pin "16") (pinfunction "SDA_16") (pintype "bidirectional"))
      (node (ref "R2") (pin "2") (pinfunction "2_2") (pintype "passive"))
      (node (ref "UC1") (pin "P$13") (pinfunction "PA04_P$13") (pintype "bidirectional"))
    )
    (net (code "77") (name "PA05") (class "Default")
      (node (ref "MAG") (pin "1") (pinfunction "SCL_1") (pintype "bidirectional"))
      (node (ref "R1") (pin "2") (pinfunction "2_2") (pintype "passive"))
      (node (ref "UC1") (pin "P$14") (pinfunction "PA05_P$14") (pintype "bidirectional"))
    )
    (net (code "78") (name "PA12") (class "Default")
      (node (ref "U$2") (pin "5") (pinfunction "SHDN_5") (pintype "bidirectional"))
      (node (ref "UC1") (pin "P$29") (pinfunction "PA12_P$29") (pintype "bidirectional"))
    )
    (net (code "79") (name "PA15") (class "Default")
      (node (ref "HEADER9M") (pin "P$6") (pinfunction "6_P$6") (pintype "passive"))
      (node (ref "UC1") (pin "P$32") (pinfunction "PA15_P$32") (pintype "bidirectional"))
    )
    (net (code "80") (name "PA16") (class "Default")
      (node (ref "HEADER9M") (pin "P$5") (pinfunction "5_P$5") (pintype "passive"))
      (node (ref "UC1") (pin "P$35") (pinfunction "PA16_P$35") (pintype "bidirectional"))
    )
    (net (code "81") (name "PA24") (class "Default")
      (node (ref "U$4") (pin "P$2") (pinfunction "A_P$2") (pintype "bidirectional"))
      (node (ref "UC1") (pin "P$45") (pinfunction "PA24_P$45") (pintype "bidirectional"))
    )
    (net (code "82") (name "PA25") (class "Default")
      (node (ref "U$5") (pin "P$4") (pinfunction "Y_P$4") (pintype "bidirectional"))
      (node (ref "UC1") (pin "P$46") (pinfunction "PA25_P$46") (pintype "bidirectional"))
    )
    (net (code "83") (name "PB01") (class "Default")
      (node (ref "RADCONNF") (pin "P$3") (pinfunction "3_P$3") (pintype "passive"))
      (node (ref "UC1") (pin "P$62") (pinfunction "PB01_P$62") (pintype "bidirectional"))
    )
    (net (code "84") (name "PB02") (class "Default")
      (node (ref "U$4") (pin "P$1") (pinfunction "OE_P$1") (pintype "bidirectional"))
      (node (ref "UC1") (pin "P$63") (pinfunction "PB02_P$63") (pintype "bidirectional"))
    )
    (net (code "85") (name "PB03") (class "Default")
      (node (ref "U$5") (pin "P$1") (pinfunction "OE_P$1") (pintype "bidirectional"))
      (node (ref "UC1") (pin "P$64") (pinfunction "PB03_P$64") (pintype "bidirectional"))
    )
    (net (code "86") (name "PB07") (class "Default")
      (node (ref "C27") (pin "1") (pinfunction "1_1") (pintype "passive"))
      (node (ref "R8") (pin "2") (pinfunction "2_2") (pintype "passive"))
      (node (ref "U$1") (pin "7") (pinfunction "IOUT_7") (pintype "bidirectional"))
      (node (ref "UC1") (pin "P$10") (pinfunction "PB07_P$10") (pintype "bidirectional"))
    )
    (net (code "87") (name "PB15") (class "Default")
      (node (ref "U$2") (pin "6") (pinfunction "POL_6") (pintype "bidirectional"))
      (node (ref "UC1") (pin "P$28") (pinfunction "PB15_P$28") (pintype "bidirectional"))
    )
    (net (code "88") (name "PWR_OUT_SIDE1") (class "Default")
      (node (ref "HEADER1F") (pin "P$6") (pinfunction "6_P$6") (pintype "passive"))
    )
    (net (code "89") (name "R2") (class "Default")
      (node (ref "RADCONNF") (pin "P$4") (pinfunction "4_P$4") (pintype "passive"))
      (node (ref "U$13") (pin "A") (pinfunction "A_A") (pintype "bidirectional"))
    )
    (net (code "90") (name "R3") (class "Default")
      (node (ref "RADCONNF") (pin "P$5") (pinfunction "5_P$5") (pintype "passive"))
      (node (ref "U$4") (pin "P$4") (pinfunction "Y_P$4") (pintype "bidirectional"))
    )
    (net (code "91") (name "R4") (class "Default")
      (node (ref "RADCONNF") (pin "P$6") (pinfunction "6_P$6") (pintype "passive"))
      (node (ref "U$12") (pin "A") (pinfunction "A_A") (pintype "bidirectional"))
    )
    (net (code "92") (name "R12") (class "Default")
      (node (ref "RADCONNF") (pin "P$1") (pinfunction "1_P$1") (pintype "passive"))
      (node (ref "U$11") (pin "A") (pinfunction "A_A") (pintype "bidirectional"))
    )
    (net (code "93") (name "R14") (class "Default")
      (node (ref "RADCONNF") (pin "P$2") (pinfunction "2_P$2") (pintype "passive"))
      (node (ref "U$5") (pin "P$2") (pinfunction "A_P$2") (pintype "bidirectional"))
    )
    (net (code "94") (name "RESETN") (class "Default")
      (node (ref "SAM-ICE") (pin "15") (pinfunction "15_15") (pintype "passive"))
      (node (ref "UC1") (pin "P$52") (pinfunction "RESETN_P$52") (pintype "input"))
    )
    (net (code "95") (name "SETC") (class "Default")
      (node (ref "C10") (pin "2") (pinfunction "2_2") (pintype "passive"))
      (node (ref "MAG") (pin "12") (pinfunction "SETC_12") (pintype "bidirectional"))
    )
    (net (code "96") (name "SP1_OUT") (class "Default")
      (node (ref "HEADER1M") (pin "P$6") (pinfunction "6_P$6") (pintype "passive"))
    )
    (net (code "97") (name "VIN") (class "Default")
      (node (ref "63001") (pin "P$5") (pinfunction "VIN_P$5") (pintype "input"))
      (node (ref "63001") (pin "P$6") (pinfunction "EN_P$6") (pintype "input"))
      (node (ref "63001") (pin "P$7") (pinfunction "PS/SYNC_P$7") (pintype "input"))
      (node (ref "63001") (pin "P$8") (pinfunction "VINA_P$8") (pintype "input"))
      (node (ref "63002") (pin "P$5") (pinfunction "VIN_P$5") (pintype "input"))
      (node (ref "63002") (pin "P$6") (pinfunction "EN_P$6") (pintype "input"))
      (node (ref "63002") (pin "P$7") (pinfunction "PS/SYNC_P$7") (pintype "input"))
      (node (ref "63002") (pin "P$8") (pinfunction "VINA_P$8") (pintype "input"))
      (node (ref "C12") (pin "1") (pinfunction "1_1") (pintype "passive"))
      (node (ref "C14") (pin "2") (pinfunction "2_2") (pintype "passive"))
      (node (ref "C16") (pin "1") (pinfunction "1_1") (pintype "passive"))
      (node (ref "C19") (pin "1") (pinfunction "1_1") (pintype "passive"))
      (node (ref "R11") (pin "1") (pinfunction "1_1") (pintype "passive"))
      (node (ref "U$1") (pin "16") (pinfunction "PWM/SYNC_16") (pintype "bidirectional"))
      (node (ref "U$1") (pin "4") (pinfunction "VIN_4") (pintype "bidirectional"))
      (node (ref "U$1") (pin "5") (pinfunction "VIN_5") (pintype "bidirectional"))
      (node (ref "U$1") (pin "6") (pinfunction "RUN_6") (pintype "bidirectional"))
      (node (ref "U$2") (pin "1") (pinfunction "SENSE+_1") (pintype "bidirectional"))
      (node (ref "U$2") (pin "8") (pinfunction "VDD_8") (pintype "bidirectional"))
    )
    (net (code "98") (name "unconnected-(HEADER1F-1-PadP$1)") (class "Default")
      (node (ref "HEADER1F") (pin "P$1") (pinfunction "1_P$1") (pintype "passive"))
    )
    (net (code "99") (name "unconnected-(HEADER1M-1-PadP$1)") (class "Default")
      (node (ref "HEADER1M") (pin "P$1") (pinfunction "1_P$1") (pintype "passive"))
    )
    (net (code "100") (name "unconnected-(HEADER7F-9-PadP$9)") (class "Default")
      (node (ref "HEADER7F") (pin "P$9") (pinfunction "9_P$9") (pintype "passive"))
    )
    (net (code "101") (name "unconnected-(HEADER7F-10-PadP$10)") (class "Default")
      (node (ref "HEADER7F") (pin "P$10") (pinfunction "10_P$10") (pintype "passive"))
    )
    (net (code "102") (name "unconnected-(HEADER7F-11-PadP$11)") (class "Default")
      (node (ref "HEADER7F") (pin "P$11") (pinfunction "11_P$11") (pintype "passive"))
    )
    (net (code "103") (name "unconnected-(HEADER7F-12-PadP$12)") (class "Default")
      (node (ref "HEADER7F") (pin "P$12") (pinfunction "12_P$12") (pintype "passive"))
    )
    (net (code "104") (name "unconnected-(HEADER7F-13-PadP$13)") (class "Default")
      (node (ref "HEADER7F") (pin "P$13") (pinfunction "13_P$13") (pintype "passive"))
    )
    (net (code "105") (name "unconnected-(HEADER7F-14-PadP$14)") (class "Default")
      (node (ref "HEADER7F") (pin "P$14") (pinfunction "14_P$14") (pintype "passive"))
    )
    (net (code "106") (name "unconnected-(HEADER7M-11-PadP$11)") (class "Default")
      (node (ref "HEADER7M") (pin "P$11") (pinfunction "11_P$11") (pintype "passive"))
    )
    (net (code "107") (name "unconnected-(HEADER7M-12-PadP$12)") (class "Default")
      (node (ref "HEADER7M") (pin "P$12") (pinfunction "12_P$12") (pintype "passive"))
    )
    (net (code "108") (name "unconnected-(HEADER9F-3-PadP$3)") (class "Default")
      (node (ref "HEADER9F") (pin "P$3") (pinfunction "3_P$3") (pintype "passive"))
    )
    (net (code "109") (name "unconnected-(HEADER9F-4-PadP$4)") (class "Default")
      (node (ref "HEADER9F") (pin "P$4") (pinfunction "4_P$4") (pintype "passive"))
    )
    (net (code "110") (name "unconnected-(HEADER9F-5-PadP$5)") (class "Default")
      (node (ref "HEADER9F") (pin "P$5") (pinfunction "5_P$5") (pintype "passive"))
    )
    (net (code "111") (name "unconnected-(HEADER9F-6-PadP$6)") (class "Default")
      (node (ref "HEADER9F") (pin "P$6") (pinfunction "6_P$6") (pintype "passive"))
    )
    (net (code "112") (name "unconnected-(HEADER9F-7-PadP$7)") (class "Default")
      (node (ref "HEADER9F") (pin "P$7") (pinfunction "7_P$7") (pintype "passive"))
    )
    (net (code "113") (name "unconnected-(HEADER9M-7-PadP$7)") (class "Default")
      (node (ref "HEADER9M") (pin "P$7") (pinfunction "7_P$7") (pintype "passive"))
    )
    (net (code "114") (name "unconnected-(MAG-NC-Pad3)") (class "Default")
      (node (ref "MAG") (pin "3") (pinfunction "NC_3") (pintype "bidirectional"))
    )
    (net (code "115") (name "unconnected-(MAG-NC-Pad5)") (class "Default")
      (node (ref "MAG") (pin "5") (pinfunction "NC_5") (pintype "bidirectional"))
    )
    (net (code "116") (name "unconnected-(MAG-NC-Pad6)") (class "Default")
      (node (ref "MAG") (pin "6") (pinfunction "NC_6") (pintype "bidirectional"))
    )
    (net (code "117") (name "unconnected-(MAG-NC-Pad7)") (class "Default")
      (node (ref "MAG") (pin "7") (pinfunction "NC_7") (pintype "bidirectional"))
    )
    (net (code "118") (name "unconnected-(MAG-NC-Pad14)") (class "Default")
      (node (ref "MAG") (pin "14") (pinfunction "NC_14") (pintype "bidirectional"))
    )
    (net (code "119") (name "unconnected-(SAM-ICE-Pad2)") (class "Default")
      (node (ref "SAM-ICE") (pin "2") (pinfunction "2_2") (pintype "passive"))
    )
    (net (code "120") (name "unconnected-(SAM-ICE-Pad3)") (class "Default")
      (node (ref "SAM-ICE") (pin "3") (pinfunction "3_3") (pintype "passive"))
    )
    (net (code "121") (name "unconnected-(SAM-ICE-Pad4)") (class "Default")
      (node (ref "SAM-ICE") (pin "4") (pinfunction "4_4") (pintype "passive"))
    )
    (net (code "122") (name "unconnected-(SAM-ICE-Pad5)") (class "Default")
      (node (ref "SAM-ICE") (pin "5") (pinfunction "5_5") (pintype "passive"))
    )
    (net (code "123") (name "unconnected-(SAM-ICE-Pad6)") (class "Default")
      (node (ref "SAM-ICE") (pin "6") (pinfunction "6_6") (pintype "passive"))
    )
    (net (code "124") (name "unconnected-(SAM-ICE-Pad8)") (class "Default")
      (node (ref "SAM-ICE") (pin "8") (pinfunction "8_8") (pintype "passive"))
    )
    (net (code "125") (name "unconnected-(SAM-ICE-Pad10)") (class "Default")
      (node (ref "SAM-ICE") (pin "10") (pinfunction "10_10") (pintype "passive"))
    )
    (net (code "126") (name "unconnected-(SAM-ICE-Pad11)") (class "Default")
      (node (ref "SAM-ICE") (pin "11") (pinfunction "11_11") (pintype "passive"))
    )
    (net (code "127") (name "unconnected-(SAM-ICE-Pad12)") (class "Default")
      (node (ref "SAM-ICE") (pin "12") (pinfunction "12_12") (pintype "passive"))
    )
    (net (code "128") (name "unconnected-(SAM-ICE-Pad13)") (class "Default")
      (node (ref "SAM-ICE") (pin "13") (pinfunction "13_13") (pintype "passive"))
    )
    (net (code "129") (name "unconnected-(SAM-ICE-Pad14)") (class "Default")
      (node (ref "SAM-ICE") (pin "14") (pinfunction "14_14") (pintype "passive"))
    )
    (net (code "130") (name "unconnected-(SAM-ICE-Pad16)") (class "Default")
      (node (ref "SAM-ICE") (pin "16") (pinfunction "16_16") (pintype "passive"))
    )
    (net (code "131") (name "unconnected-(SAM-ICE-Pad17)") (class "Default")
      (node (ref "SAM-ICE") (pin "17") (pinfunction "17_17") (pintype "passive"))
    )
    (net (code "132") (name "unconnected-(SAM-ICE-Pad18)") (class "Default")
      (node (ref "SAM-ICE") (pin "18") (pinfunction "18_18") (pintype "passive"))
    )
    (net (code "133") (name "unconnected-(SAM-ICE-Pad19)") (class "Default")
      (node (ref "SAM-ICE") (pin "19") (pinfunction "19_19") (pintype "passive"))
    )
    (net (code "134") (name "unconnected-(SAM-ICE-Pad20)") (class "Default")
      (node (ref "SAM-ICE") (pin "20") (pinfunction "20_20") (pintype "passive"))
    )
    (net (code "135") (name "unconnected-(U$2-CLR-Pad9)") (class "Default")
      (node (ref "U$2") (pin "9") (pinfunction "CLR_9") (pintype "bidirectional"))
    )
    (net (code "136") (name "unconnected-(UC1-PA02-PadP$3)") (class "Default")
      (node (ref "UC1") (pin "P$3") (pinfunction "PA02_P$3") (pintype "bidirectional"))
    )
    (net (code "137") (name "unconnected-(UC1-PA03-PadP$4)") (class "Default")
      (node (ref "UC1") (pin "P$4") (pinfunction "PA03_P$4") (pintype "bidirectional"))
    )
    (net (code "138") (name "unconnected-(UC1-PA07-PadP$16)") (class "Default")
      (node (ref "UC1") (pin "P$16") (pinfunction "PA07_P$16") (pintype "bidirectional"))
    )
    (net (code "139") (name "unconnected-(UC1-PA08-PadP$17)") (class "Default")
      (node (ref "UC1") (pin "P$17") (pinfunction "PA08_P$17") (pintype "bidirectional"))
    )
    (net (code "140") (name "unconnected-(UC1-PA09-PadP$18)") (class "Default")
      (node (ref "UC1") (pin "P$18") (pinfunction "PA09_P$18") (pintype "bidirectional"))
    )
    (net (code "141") (name "unconnected-(UC1-PA10-PadP$19)") (class "Default")
      (node (ref "UC1") (pin "P$19") (pinfunction "PA10_P$19") (pintype "bidirectional"))
    )
    (net (code "142") (name "unconnected-(UC1-PA11-PadP$20)") (class "Default")
      (node (ref "UC1") (pin "P$20") (pinfunction "PA11_P$20") (pintype "bidirectional"))
    )
    (net (code "143") (name "unconnected-(UC1-PA27-PadP$51)") (class "Default")
      (node (ref "UC1") (pin "P$51") (pinfunction "PA27_P$51") (pintype "bidirectional"))
    )
    (net (code "144") (name "unconnected-(UC1-PA28-PadP$53)") (class "Default")
      (node (ref "UC1") (pin "P$53") (pinfunction "PA28_P$53") (pintype "bidirectional"))
    )
    (net (code "145") (name "unconnected-(UC1-PB06-PadP$9)") (class "Default")
      (node (ref "UC1") (pin "P$9") (pinfunction "PB06_P$9") (pintype "bidirectional"))
    )
    (net (code "146") (name "unconnected-(UC1-PB10-PadP$23)") (class "Default")
      (node (ref "UC1") (pin "P$23") (pinfunction "PB10_P$23") (pintype "bidirectional"))
    )
    (net (code "147") (name "unconnected-(UC1-PB11-PadP$24)") (class "Default")
      (node (ref "UC1") (pin "P$24") (pinfunction "PB11_P$24") (pintype "bidirectional"))
    )
    (net (code "148") (name "unconnected-(UC1-PB12-PadP$25)") (class "Default")
      (node (ref "UC1") (pin "P$25") (pinfunction "PB12_P$25") (pintype "bidirectional"))
    )
    (net (code "149") (name "unconnected-(UC1-PB13-PadP$26)") (class "Default")
      (node (ref "UC1") (pin "P$26") (pinfunction "PB13_P$26") (pintype "bidirectional"))
    )
    (net (code "150") (name "unconnected-(UC1-PB14-PadP$27)") (class "Default")
      (node (ref "UC1") (pin "P$27") (pinfunction "PB14_P$27") (pintype "bidirectional"))
    )
    (net (code "151") (name "unconnected-(UC1-PB22-PadP$49)") (class "Default")
      (node (ref "UC1") (pin "P$49") (pinfunction "PB22_P$49") (pintype "bidirectional"))
    )
    (net (code "152") (name "unconnected-(UC1-PB23-PadP$50)") (class "Default")
      (node (ref "UC1") (pin "P$50") (pinfunction "PB23_P$50") (pintype "bidirectional"))
    )
    (net (code "153") (name "unconnected-(UC1-PB30-PadP$59)") (class "Default")
      (node (ref "UC1") (pin "P$59") (pinfunction "PB30_P$59") (pintype "bidirectional"))
    )
    (net (code "154") (name "unconnected-(UC1-PB31-PadP$60)") (class "Default")
      (node (ref "UC1") (pin "P$60") (pinfunction "PB31_P$60") (pintype "bidirectional"))
    )
  )
)
